# Mech_Interface_Port.net
KiCad netlist of a schematic drawn in Altium Designer
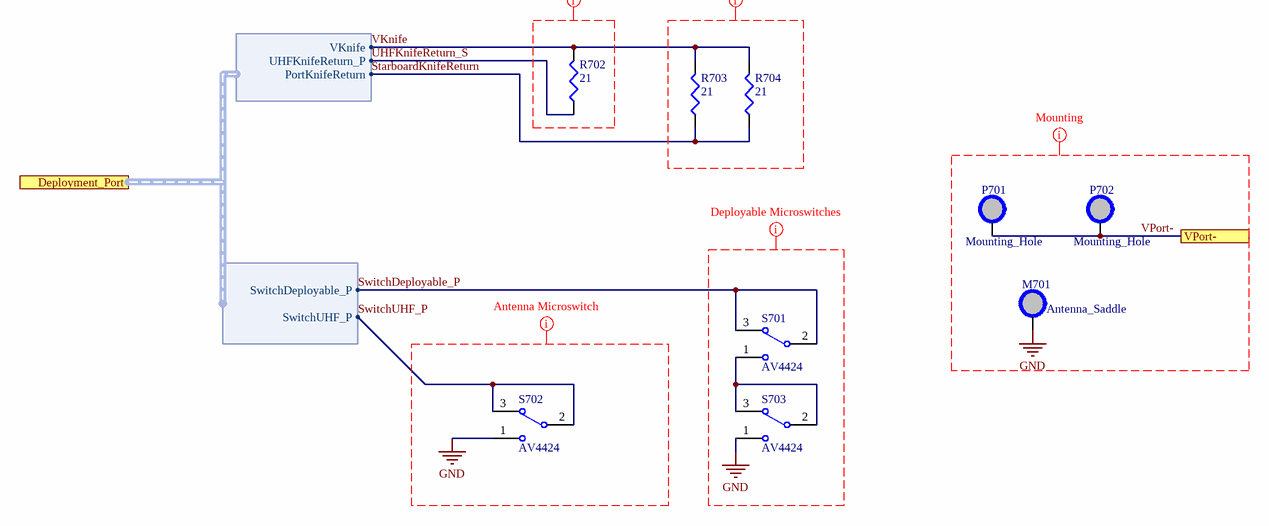
[diagram p0: Mech_Interface_Port.SchDoc]

(export (version "E")
  (design (tool "Eeschema 10.0.6"))
  (components
    (comp (ref "M701")
      (value "Antenna_Saddle")
      (footprint "ANTENNA_SADDLE")
      (fields
        (field (name "PART NUMBER") "PXX-ABS-00001")
        (field (name "MANUFACTURER PART NUMBER") "Custom")
        (field (name "PUBLISHER") "AlbertaSat")
      )
      (libsource (lib "Database") (part "Mounting_Hole"))
    )
    (comp (ref "P701")
      (value "Mounting_Hole")
      (footprint "DEPHINGE_MOUNTING_HOLE_BODY")
      (fields
        (field (name "PART NUMBER") "PXX-ABS-00004")
        (field (name "MANUFACTURER PART NUMBER") "Custom")
        (field (name "PUBLISHER") "AlbertaSat")
      )
      (libsource (lib "Database") (part "Mounting_Hole"))
    )
    (comp (ref "P702")
      (value "Mounting_Hole")
      (footprint "DEPHINGE_MOUNTING_HOLE_BODY")
      (fields
        (field (name "PART NUMBER") "PXX-ABS-00004")
        (field (name "MANUFACTURER PART NUMBER") "Custom")
        (field (name "PUBLISHER") "AlbertaSat")
      )
      (libsource (lib "Database") (part "Mounting_Hole"))
    )
    (comp (ref "R702")
      (value "21")
      (footprint "VSH-CPF1")
      (description "21 Ohms ±1% 1W Through Hole Resistor Axial Flame Proof, Moisture Resistant, Safety Metal Film")
      (fields
        (field (name "PART NUMBER") "PR-VSH-00317")
        (field (name "MANUFACTURER PART NUMBER") "CPF121R000FKEE6")
        (field (name "PUBLISHER") "AlbertaSat")
      )
      (libsource (lib "Database") (part "Res3"))
    )
    (comp (ref "R703")
      (value "21")
      (footprint "VSH-CPF1")
      (description "21 Ohms ±1% 1W Through Hole Resistor Axial Flame Proof, Moisture Resistant, Safety Metal Film")
      (fields
        (field (name "PART NUMBER") "PR-VSH-00317")
        (field (name "MANUFACTURER PART NUMBER") "CPF121R000FKEE6")
        (field (name "PUBLISHER") "AlbertaSat")
      )
      (libsource (lib "Database") (part "Res3"))
    )
    (comp (ref "R704")
      (value "21")
      (footprint "VSH-CPF1")
      (description "21 Ohms ±1% 1W Through Hole Resistor Axial Flame Proof, Moisture Resistant, Safety Metal Film")
      (fields
        (field (name "PART NUMBER") "PR-VSH-00317")
        (field (name "MANUFACTURER PART NUMBER") "CPF121R000FKEE6")
        (field (name "PUBLISHER") "AlbertaSat")
      )
      (libsource (lib "Database") (part "Res3"))
    )
    (comp (ref "S701")
      (value "AV4424")
      (footprint "PANA-AV4424")
      (description "SWITCH SNAP ACT SPDT 500MA 30V")
      (fields (field (name "PART NUMBER") "20035"))
      (libsource (lib "Database") (part "SW-SPDT"))
    )
    (comp (ref "S702")
      (value "AV4424")
      (footprint "PANA-AV4424")
      (description "SWITCH SNAP ACT SPDT 500MA 30V")
      (fields (field (name "PART NUMBER") "20035"))
      (libsource (lib "Database") (part "SW-SPDT"))
    )
    (comp (ref "S703")
      (value "AV4424")
      (footprint "PANA-AV4424")
      (description "SWITCH SNAP ACT SPDT 500MA 30V")
      (fields (field (name "PART NUMBER") "20035"))
      (libsource (lib "Database") (part "SW-SPDT"))
    )
  )
  (nets
    (net (code "2") (name "/StarboardKnifeReturn") (class "Default")
      (node (ref "R703") (pin "1") (pinfunction "1_1") (pintype "passive"))
      (node (ref "R704") (pin "1") (pinfunction "1_1") (pintype "passive"))
    )
    (net (code "3") (name "/SwitchDeployable_P") (class "Default")
      (node (ref "S701") (pin "2") (pinfunction "COM_2") (pintype "passive"))
      (node (ref "S701") (pin "3") (pinfunction "NC_3") (pintype "passive"))
    )
    (net (code "4") (name "/SwitchUHF_P") (class "Default")
      (node (ref "S702") (pin "2") (pinfunction "COM_2") (pintype "passive"))
      (node (ref "S702") (pin "3") (pinfunction "NC_3") (pintype "passive"))
    )
    (net (code "5") (name "/UHFKnifeReturn_S") (class "Default")
      (node (ref "R702") (pin "1") (pinfunction "1_1") (pintype "passive"))
    )
    (net (code "6") (name "/VKnife") (class "Default")
      (node (ref "R702") (pin "2") (pinfunction "2_2") (pintype "passive"))
      (node (ref "R703") (pin "2") (pinfunction "2_2") (pintype "passive"))
      (node (ref "R704") (pin "2") (pinfunction "2_2") (pintype "passive"))
    )
    (net (code "7") (name "/VPort-") (class "Default")
      (node (ref "P701") (pin "1") (pinfunction "0_1") (pintype "passive"))
      (node (ref "P702") (pin "1") (pinfunction "0_1") (pintype "passive"))
    )
    (net (code "9") (name "GND") (class "Default")
      (node (ref "M701") (pin "1") (pinfunction "0_1") (pintype "passive"))
      (node (ref "S702") (pin "1") (pinfunction "NO_1") (pintype "passive"))
      (node (ref "S703") (pin "1") (pinfunction "NO_1") (pintype "passive"))
    )
    (net (code "10") (name "Net-(S701-NO)") (class "Default")
      (node (ref "S701") (pin "1") (pinfunction "NO_1") (pintype "passive"))
      (node (ref "S703") (pin "2") (pinfunction "COM_2") (pintype "passive"))
      (node (ref "S703") (pin "3") (pinfunction "NC_3") (pintype "passive"))
    )
  )
)
